# main.net
KiCad netlist of a schematic drawn in EAGLE
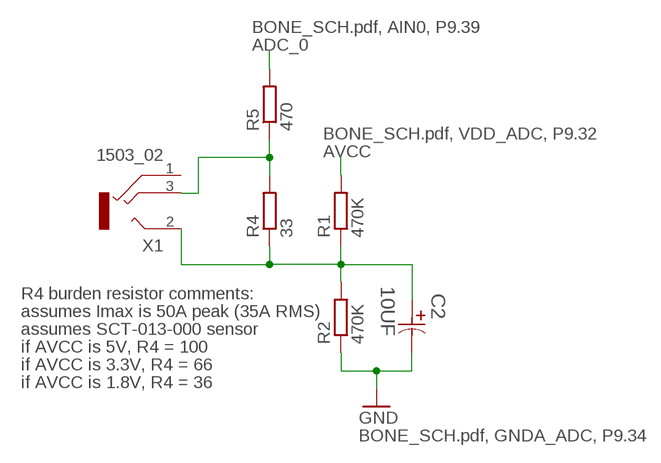
[diagram p0: schematic, sheet 1]

(export (version "E")
  (design (tool "Eeschema 10.0.6"))
  (components
    (comp (ref "C2")
      (value "10UF")
      (footprint "eagle-import:CAPAE530X610N")
      (fields (field (name "MPN") "EEE-1EA100SR") (field (name "TOLERANCE") " 20%"))
      (libsource (lib "eagle-import") (part "EEE--CASE-C1EA100SR"))
    )
    (comp (ref "R1")
      (value "470K")
      (footprint "eagle-import:M1206")
      (libsource (lib "eagle-import") (part "R-EU_M1206"))
    )
    (comp (ref "R2")
      (value "470K")
      (footprint "eagle-import:M1206")
      (libsource (lib "eagle-import") (part "R-EU_M1206"))
    )
    (comp (ref "R4")
      (value "33")
      (footprint "eagle-import:M1206")
      (libsource (lib "eagle-import") (part "R-EU_M1206"))
    )
    (comp (ref "R5")
      (value "470")
      (footprint "eagle-import:M1206")
      (libsource (lib "eagle-import") (part "R-EU_M1206"))
    )
    (comp (ref "X1")
      (value "1503_02")
      (footprint "eagle-import:1503_02")
      (libsource (lib "eagle-import") (part "1503_02"))
    )
  )
  (nets
    (net (code "1") (name "/ADC_0") (class "Default")
      (node (ref "R5") (pin "2") (pinfunction "2_2") (pintype "passive"))
    )
    (net (code "2") (name "/AVCC") (class "Default")
      (node (ref "R1") (pin "2") (pinfunction "2_2") (pintype "passive"))
    )
    (net (code "3") (name "GND") (class "Default")
      (node (ref "C2") (pin "2") (pinfunction "2_2") (pintype "passive"))
      (node (ref "R2") (pin "1") (pinfunction "1_1") (pintype "passive"))
    )
    (net (code "4") (name "Net-(C2-Pad1)") (class "Default")
      (node (ref "C2") (pin "1") (pinfunction "1_1") (pintype "passive"))
      (node (ref "R1") (pin "1") (pinfunction "1_1") (pintype "passive"))
      (node (ref "R2") (pin "2") (pinfunction "2_2") (pintype "passive"))
      (node (ref "R4") (pin "1") (pinfunction "1_1") (pintype "passive"))
      (node (ref "X1") (pin "2") (pinfunction "2_2") (pintype "passive"))
    )
    (net (code "5") (name "Net-(R4-Pad2)") (class "Default")
      (node (ref "R4") (pin "2") (pinfunction "2_2") (pintype "passive"))
      (node (ref "R5") (pin "1") (pinfunction "1_1") (pintype "passive"))
      (node (ref "X1") (pin "3") (pinfunction "3_3") (pintype "passive"))
    )
    (net (code "6") (name "unconnected-(X1-2-Pad2@2)") (class "Default")
      (node (ref "X1") (pin "2@2") (pinfunction "2_2@2") (pintype "passive"))
    )
    (net (code "7") (name "unconnected-(X1-Pad1)") (class "Default")
      (node (ref "X1") (pin "1") (pinfunction "1_1") (pintype "passive"))
    )
  )
)
